# esp32_cam_rev_A.net
KiCad netlist of a schematic drawn in EAGLE
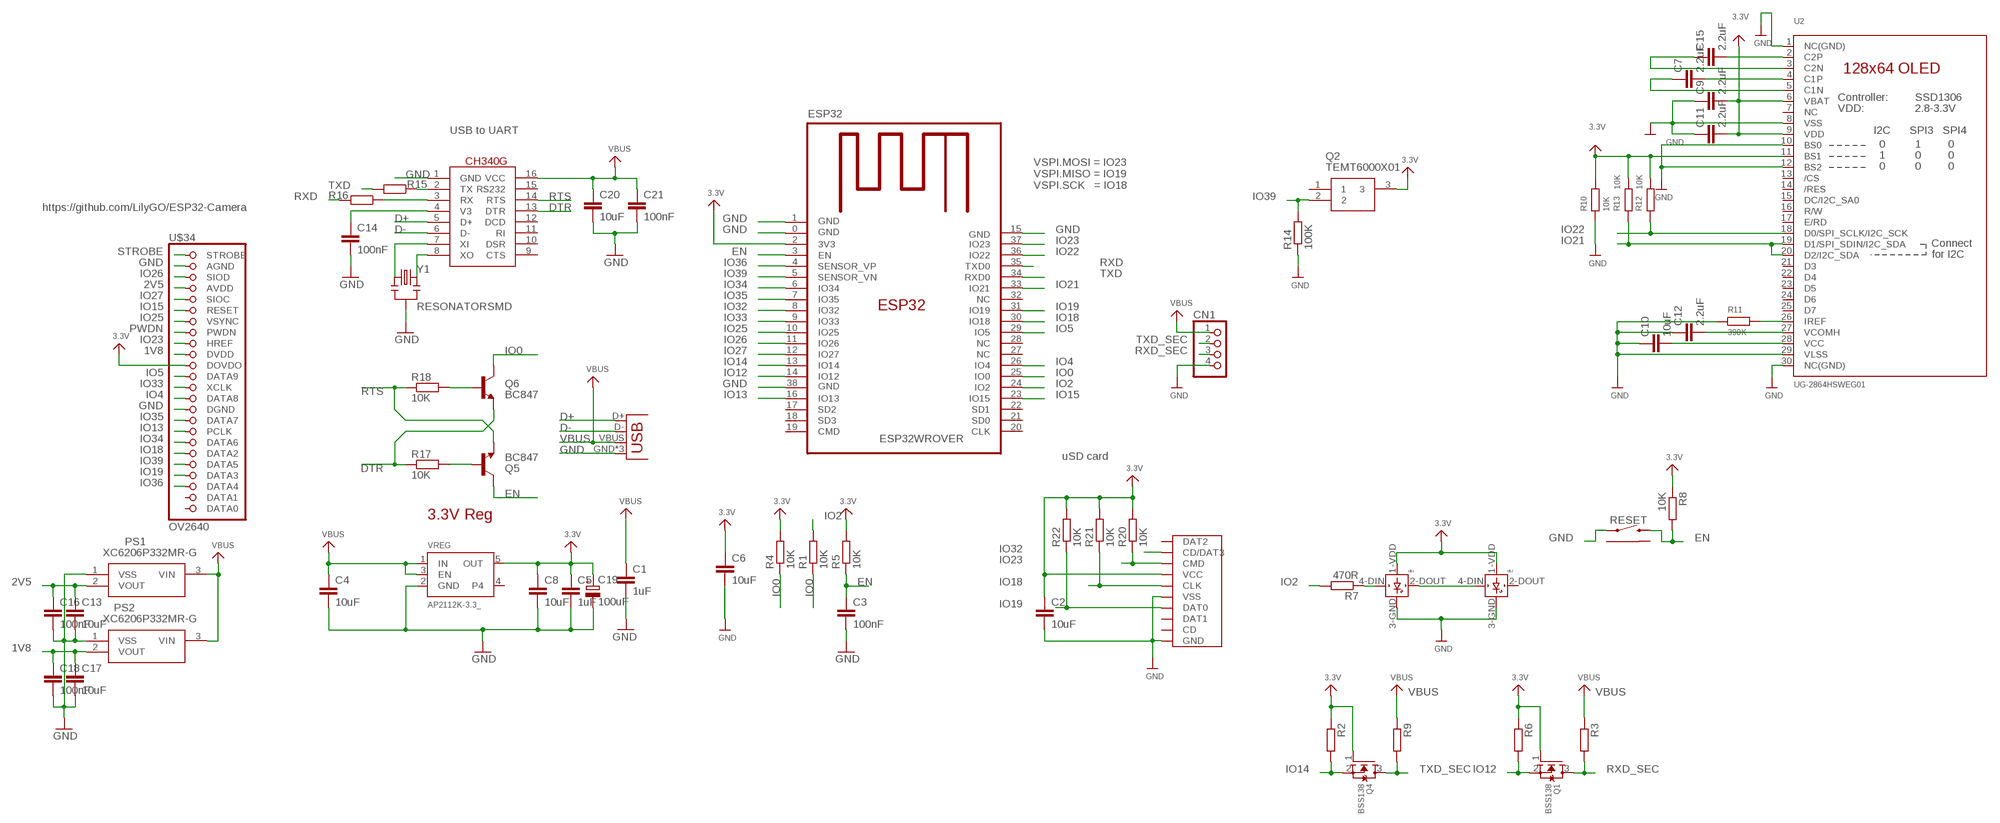
[diagram p0: schematic, sheet 1]

(export (version "E")
  (design (tool "Eeschema 10.0.6"))
  (components
    (comp (ref "C1")
      (value "1uF")
      (footprint "eagle-import:C0805K")
      (libsource (lib "eagle-import") (part "C-EUC0805K"))
    )
    (comp (ref "C2")
      (value "10uF")
      (footprint "eagle-import:C0805K")
      (libsource (lib "eagle-import") (part "C-EUC0805K"))
    )
    (comp (ref "C3")
      (value "100nF")
      (footprint "eagle-import:C0805K")
      (libsource (lib "eagle-import") (part "C-EUC0805K"))
    )
    (comp (ref "C4")
      (value "10uF")
      (footprint "eagle-import:C0805K")
      (libsource (lib "eagle-import") (part "C-EUC0805K"))
    )
    (comp (ref "C5")
      (value "1uF")
      (footprint "eagle-import:C0805K")
      (libsource (lib "eagle-import") (part "C-EUC0805K"))
    )
    (comp (ref "C6")
      (value "10uF")
      (footprint "eagle-import:C0805K")
      (libsource (lib "eagle-import") (part "C-EUC0805K"))
    )
    (comp (ref "C7")
      (value "2.2uF")
      (footprint "eagle-import:C0805")
      (libsource (lib "eagle-import") (part "C-EUC0805"))
    )
    (comp (ref "C8")
      (value "10uF")
      (footprint "eagle-import:C0805K")
      (libsource (lib "eagle-import") (part "C-EUC0805K"))
    )
    (comp (ref "C9")
      (value "2.2uF")
      (footprint "eagle-import:C0805")
      (libsource (lib "eagle-import") (part "C-EUC0805"))
    )
    (comp (ref "C10")
      (value "10uF")
      (footprint "eagle-import:C0805")
      (libsource (lib "eagle-import") (part "C-EUC0805"))
    )
    (comp (ref "C11")
      (value "2.2uF")
      (footprint "eagle-import:C0805")
      (libsource (lib "eagle-import") (part "C-EUC0805"))
    )
    (comp (ref "C12")
      (value "2.2uF")
      (footprint "eagle-import:C0805")
      (libsource (lib "eagle-import") (part "C-EUC0805"))
    )
    (comp (ref "C13")
      (value "10uF")
      (footprint "eagle-import:C0805K")
      (libsource (lib "eagle-import") (part "C-EUC0805K"))
    )
    (comp (ref "C14")
      (value "100nF")
      (footprint "eagle-import:C0805K")
      (libsource (lib "eagle-import") (part "C-EUC0805K"))
    )
    (comp (ref "C15")
      (value "2.2uF")
      (footprint "eagle-import:C0805")
      (libsource (lib "eagle-import") (part "C-EUC0805"))
    )
    (comp (ref "C16")
      (value "100nF")
      (footprint "eagle-import:C0805K")
      (libsource (lib "eagle-import") (part "C-EUC0805K"))
    )
    (comp (ref "C17")
      (value "10uF")
      (footprint "eagle-import:C0805K")
      (libsource (lib "eagle-import") (part "C-EUC0805K"))
    )
    (comp (ref "C18")
      (value "100nF")
      (footprint "eagle-import:C0805K")
      (libsource (lib "eagle-import") (part "C-EUC0805K"))
    )
    (comp (ref "C19")
      (value "100uF")
      (footprint "eagle-import:CT6032")
      (libsource (lib "eagle-import") (part "CPOL-EUCT6032"))
    )
    (comp (ref "C20")
      (value "10uF")
      (footprint "eagle-import:C0805K")
      (libsource (lib "eagle-import") (part "C-EUC0805K"))
    )
    (comp (ref "C21")
      (value "100nF")
      (footprint "eagle-import:C0805K")
      (libsource (lib "eagle-import") (part "C-EUC0805K"))
    )
    (comp (ref "CN1")
      (value "JST_PH4")
      (footprint "eagle-import:JSTPH4")
      (libsource (lib "eagle-import") (part "JST_PH4"))
    )
    (comp (ref "ESP32")
      (value "ESP32WROVER")
      (footprint "eagle-import:ESP32WROVER")
      (libsource (lib "eagle-import") (part "ESP32WROVER"))
    )
    (comp (ref "PS1")
      (value "XC6206P332MR-G")
      (footprint "eagle-import:SOT95P280X130-3N")
      (fields (field (name "MOUSER_PART_NUMBER") "865-XC6206P332MR-G"))
      (libsource (lib "eagle-import") (part "XC6206P332MR-G"))
    )
    (comp (ref "PS2")
      (value "XC6206P332MR-G")
      (footprint "eagle-import:SOT95P280X130-3N")
      (fields (field (name "MOUSER_PART_NUMBER") "865-XC6206P332MR-G"))
      (libsource (lib "eagle-import") (part "XC6206P332MR-G"))
    )
    (comp (ref "Q1")
      (value "BSS138")
      (footprint "eagle-import:SOT95P240X110-3")
      (libsource (lib "eagle-import") (part "MOSFET_N_"))
    )
    (comp (ref "Q2")
      (value "TEMT6000X01")
      (footprint "eagle-import:TEMT6000X01")
      (fields (field (name "MOUSER_PART_NUMBER") "78-TEMT6000"))
      (libsource (lib "eagle-import") (part "TEMT6000X01"))
    )
    (comp (ref "Q4")
      (value "BSS138")
      (footprint "eagle-import:SOT95P240X110-3")
      (libsource (lib "eagle-import") (part "MOSFET_N_"))
    )
    (comp (ref "Q5")
      (value "BC847")
      (footprint "eagle-import:SOT23-3")
      (libsource (lib "eagle-import") (part "TRANSISTOR_NPNSOT23-3"))
    )
    (comp (ref "Q6")
      (value "BC847")
      (footprint "eagle-import:SOT23-3")
      (libsource (lib "eagle-import") (part "TRANSISTOR_NPNSOT23-3"))
    )
    (comp (ref "R1")
      (value "10K")
      (footprint "eagle-import:R0805")
      (libsource (lib "eagle-import") (part "R-EU_R0805"))
    )
    (comp (ref "R2")
      (value "10K")
      (footprint "eagle-import:R0805")
      (libsource (lib "eagle-import") (part "R-EU_R0805"))
    )
    (comp (ref "R3")
      (value "10K")
      (footprint "eagle-import:R0805")
      (libsource (lib "eagle-import") (part "R-EU_R0805"))
    )
    (comp (ref "R4")
      (value "10K")
      (footprint "eagle-import:R0805")
      (libsource (lib "eagle-import") (part "R-EU_R0805"))
    )
    (comp (ref "R5")
      (value "10K")
      (footprint "eagle-import:R0805")
      (libsource (lib "eagle-import") (part "R-EU_R0805"))
    )
    (comp (ref "R6")
      (value "10K")
      (footprint "eagle-import:R0805")
      (libsource (lib "eagle-import") (part "R-EU_R0805"))
    )
    (comp (ref "R7")
      (value "470R")
      (footprint "eagle-import:R0805")
      (libsource (lib "eagle-import") (part "R-EU_R0805"))
    )
    (comp (ref "R8")
      (value "10K")
      (footprint "eagle-import:R0805")
      (libsource (lib "eagle-import") (part "R-EU_R0805"))
    )
    (comp (ref "R9")
      (value "10K")
      (footprint "eagle-import:R0805")
      (libsource (lib "eagle-import") (part "R-EU_R0805"))
    )
    (comp (ref "R10")
      (value "10K")
      (footprint "eagle-import:R0805")
      (libsource (lib "eagle-import") (part "R-EU_R0805"))
    )
    (comp (ref "R11")
      (value "390K")
      (footprint "eagle-import:R0805")
      (libsource (lib "eagle-import") (part "R-EU_R0805"))
    )
    (comp (ref "R12")
      (value "10K")
      (footprint "eagle-import:R0805")
      (libsource (lib "eagle-import") (part "R-EU_R0805"))
    )
    (comp (ref "R13")
      (value "10K")
      (footprint "eagle-import:R0805")
      (libsource (lib "eagle-import") (part "R-EU_R0805"))
    )
    (comp (ref "R14")
      (value "100K")
      (footprint "eagle-import:R0805")
      (libsource (lib "eagle-import") (part "R-EU_R0805"))
    )
    (comp (ref "R15")
      (value "470R")
      (footprint "eagle-import:R0805")
      (libsource (lib "eagle-import") (part "R-EU_R0805"))
    )
    (comp (ref "R16")
      (value "470R")
      (footprint "eagle-import:R0805")
      (libsource (lib "eagle-import") (part "R-EU_R0805"))
    )
    (comp (ref "R17")
      (value "10K")
      (footprint "eagle-import:R0805")
      (libsource (lib "eagle-import") (part "R-EU_R0805"))
    )
    (comp (ref "R18")
      (value "10K")
      (footprint "eagle-import:R0805")
      (libsource (lib "eagle-import") (part "R-EU_R0805"))
    )
    (comp (ref "R20")
      (value "10K")
      (footprint "eagle-import:R0805")
      (libsource (lib "eagle-import") (part "R-EU_R0805"))
    )
    (comp (ref "R21")
      (value "10K")
      (footprint "eagle-import:R0805")
      (libsource (lib "eagle-import") (part "R-EU_R0805"))
    )
    (comp (ref "R22")
      (value "10K")
      (footprint "eagle-import:R0805")
      (libsource (lib "eagle-import") (part "R-EU_R0805"))
    )
    (comp (ref "RESET")
      (value "TACTILE_SWITCH_RIGHT_ANGLE_THT\"")
      (footprint "eagle-import:TACTILE_SWITCH_RIGHT_ANGLE_THT")
      (libsource (lib "eagle-import") (part "TACTILE_SWITCH_RIGHT_ANGLE_THT{dblquote}"))
    )
    (comp (ref "SD_CARD")
      (value "MICRO_SD_CARD\"")
      (footprint "eagle-import:TFP09-2--12B")
      (libsource (lib "eagle-import") (part "MICRO_SD_CARD{dblquote}"))
    )
    (comp (ref "U$1")
      (value "WS2812B")
      (footprint "eagle-import:WS2812B_5050")
      (libsource (lib "eagle-import") (part "WS2812B"))
    )
    (comp (ref "U$2")
      (value "WS2812B")
      (footprint "eagle-import:WS2812B_5050")
      (libsource (lib "eagle-import") (part "WS2812B"))
    )
    (comp (ref "U$23")
      (value "CH340G")
      (footprint "eagle-import:SO16")
      (libsource (lib "eagle-import") (part "CH340G"))
    )
    (comp (ref "U$34")
      (value "OV2640")
      (footprint "eagle-import:FH12-24S-0.5SH")
      (libsource (lib "eagle-import") (part "OV2640"))
    )
    (comp (ref "U2")
      (value "UG-2864HSWEG01")
      (footprint "eagle-import:UG-2864HSWEG01_1.3_WRAPAROUND_MIRRORED")
      (libsource (lib "eagle-import") (part "DISP_OLED_UG-2864HSWEG01_"))
    )
    (comp (ref "USB")
      (value "USB_MICRO_ATTEND_")
      (footprint "eagle-import:USB_MICRO")
      (libsource (lib "eagle-import") (part "USB_MICRO_ATTEND_"))
    )
    (comp (ref "VREG")
      (value "AP2112K-3.3_")
      (footprint "eagle-import:SOT95P290X120-5")
      (libsource (lib "eagle-import") (part "AP2112K-3.3_"))
    )
    (comp (ref "Y1")
      (value "RESONATORSMD")
      (footprint "eagle-import:RESONATOR-SMD")
      (libsource (lib "eagle-import") (part "RESONATORSMD"))
    )
  )
  (nets
    (net (code "1") (name "/1V8") (class "Default")
      (node (ref "C17") (pin "1") (pinfunction "1_1") (pintype "passive"))
      (node (ref "C18") (pin "1") (pinfunction "1_1") (pintype "passive"))
      (node (ref "PS2") (pin "2") (pinfunction "VOUT_2") (pintype "power_in"))
      (node (ref "U$34") (pin "10") (pinfunction "DVDD_10") (pintype "passive"))
    )
    (net (code "2") (name "/2V5") (class "Default")
      (node (ref "C13") (pin "1") (pinfunction "1_1") (pintype "passive"))
      (node (ref "C16") (pin "1") (pinfunction "1_1") (pintype "passive"))
      (node (ref "PS1") (pin "2") (pinfunction "VOUT_2") (pintype "power_in"))
      (node (ref "U$34") (pin "4") (pinfunction "AVDD_4") (pintype "passive"))
    )
    (net (code "3") (name "/D+") (class "Default")
      (node (ref "U$23") (pin "5") (pinfunction "D+_5") (pintype "bidirectional"))
      (node (ref "USB") (pin "D+") (pinfunction "D+_D+") (pintype "bidirectional"))
    )
    (net (code "4") (name "/D-") (class "Default")
      (node (ref "U$23") (pin "6") (pinfunction "D-_6") (pintype "bidirectional"))
      (node (ref "USB") (pin "D-") (pinfunction "D-_D-") (pintype "bidirectional"))
    )
    (net (code "5") (name "/DTR") (class "Default")
      (node (ref "Q6") (pin "2") (pinfunction "E_2") (pintype "passive"))
      (node (ref "R17") (pin "1") (pinfunction "1_1") (pintype "passive"))
      (node (ref "U$23") (pin "13") (pinfunction "DTR_13") (pintype "bidirectional"))
    )
    (net (code "6") (name "/EN") (class "Default")
      (node (ref "C3") (pin "1") (pinfunction "1_1") (pintype "passive"))
      (node (ref "ESP32") (pin "3") (pinfunction "EN_3") (pintype "bidirectional"))
      (node (ref "Q5") (pin "3") (pinfunction "C_3") (pintype "passive"))
      (node (ref "R5") (pin "1") (pinfunction "1_1") (pintype "passive"))
      (node (ref "R8") (pin "2") (pinfunction "2_2") (pintype "passive"))
      (node (ref "RESET") (pin "2") (pinfunction "2_2") (pintype "passive"))
    )
    (net (code "7") (name "/IO0") (class "Default")
      (node (ref "ESP32") (pin "25") (pinfunction "IO0_25") (pintype "bidirectional"))
      (node (ref "Q6") (pin "3") (pinfunction "C_3") (pintype "passive"))
      (node (ref "R1") (pin "1") (pinfunction "1_1") (pintype "passive"))
      (node (ref "R4") (pin "1") (pinfunction "1_1") (pintype "passive"))
    )
    (net (code "8") (name "/IO2") (class "Default")
      (node (ref "ESP32") (pin "24") (pinfunction "IO2_24") (pintype "bidirectional"))
      (node (ref "R1") (pin "2") (pinfunction "2_2") (pintype "passive"))
      (node (ref "R7") (pin "2") (pinfunction "2_2") (pintype "passive"))
    )
    (net (code "9") (name "/IO4") (class "Default")
      (node (ref "ESP32") (pin "26") (pinfunction "IO4_26") (pintype "bidirectional"))
      (node (ref "U$34") (pin "14") (pinfunction "DATA8_14") (pintype "passive"))
    )
    (net (code "10") (name "/IO5") (class "Default")
      (node (ref "ESP32") (pin "29") (pinfunction "IO5_29") (pintype "bidirectional"))
      (node (ref "U$34") (pin "12") (pinfunction "DATA9_12") (pintype "passive"))
    )
    (net (code "11") (name "/IO12") (class "Default")
      (node (ref "ESP32") (pin "14") (pinfunction "IO12_14") (pintype "bidirectional"))
      (node (ref "Q1") (pin "2") (pinfunction "S_2") (pintype "bidirectional"))
      (node (ref "R6") (pin "2") (pinfunction "2_2") (pintype "passive"))
    )
    (net (code "12") (name "/IO13") (class "Default")
      (node (ref "ESP32") (pin "16") (pinfunction "IO13_16") (pintype "bidirectional"))
      (node (ref "U$34") (pin "17") (pinfunction "PCLK_17") (pintype "passive"))
    )
    (net (code "13") (name "/IO14") (class "Default")
      (node (ref "ESP32") (pin "13") (pinfunction "IO14_13") (pintype "bidirectional"))
      (node (ref "Q4") (pin "2") (pinfunction "S_2") (pintype "bidirectional"))
      (node (ref "R2") (pin "2") (pinfunction "2_2") (pintype "passive"))
    )
    (net (code "14") (name "/IO15") (class "Default")
      (node (ref "ESP32") (pin "23") (pinfunction "IO15_23") (pintype "bidirectional"))
      (node (ref "U$34") (pin "6") (pinfunction "RESET_6") (pintype "passive"))
    )
    (net (code "15") (name "/IO18") (class "Default")
      (node (ref "ESP32") (pin "30") (pinfunction "IO18_30") (pintype "bidirectional"))
      (node (ref "R21") (pin "1") (pinfunction "1_1") (pintype "passive"))
      (node (ref "SD_CARD") (pin "CLK") (pinfunction "CLK_CLK") (pintype "bidirectional"))
      (node (ref "U$34") (pin "19") (pinfunction "DATA2_19") (pintype "passive"))
    )
    (net (code "16") (name "/IO19") (class "Default")
      (node (ref "ESP32") (pin "31") (pinfunction "IO19_31") (pintype "bidirectional"))
      (node (ref "R22") (pin "1") (pinfunction "1_1") (pintype "passive"))
      (node (ref "SD_CARD") (pin "DAT0") (pinfunction "DAT0_DAT0") (pintype "bidirectional"))
      (node (ref "U$34") (pin "21") (pinfunction "DATA3_21") (pintype "passive"))
    )
    (net (code "17") (name "/IO21") (class "Default")
      (node (ref "ESP32") (pin "33") (pinfunction "IO21_33") (pintype "bidirectional"))
      (node (ref "R13") (pin "1") (pinfunction "1_1") (pintype "passive"))
      (node (ref "U2") (pin "19") (pinfunction "D1/SPI_SDIN/I2C_SDA_19") (pintype "bidirectional"))
      (node (ref "U2") (pin "20") (pinfunction "D2/I2C_SDA_20") (pintype "bidirectional"))
    )
    (net (code "18") (name "/IO22") (class "Default")
      (node (ref "ESP32") (pin "36") (pinfunction "IO22_36") (pintype "bidirectional"))
      (node (ref "R12") (pin "1") (pinfunction "1_1") (pintype "passive"))
      (node (ref "U2") (pin "18") (pinfunction "D0/SPI_SCLK/I2C_SCK_18") (pintype "bidirectional"))
    )
    (net (code "19") (name "/IO23") (class "Default")
      (node (ref "ESP32") (pin "37") (pinfunction "IO23_37") (pintype "bidirectional"))
      (node (ref "R20") (pin "1") (pinfunction "1_1") (pintype "passive"))
      (node (ref "SD_CARD") (pin "CMD") (pinfunction "CMD_CMD") (pintype "bidirectional"))
      (node (ref "U$34") (pin "9") (pinfunction "HREF_9") (pintype "passive"))
    )
    (net (code "20") (name "/IO25") (class "Default")
      (node (ref "ESP32") (pin "10") (pinfunction "IO25_10") (pintype "bidirectional"))
      (node (ref "U$34") (pin "7") (pinfunction "VSYNC_7") (pintype "passive"))
    )
    (net (code "21") (name "/IO26") (class "Default")
      (node (ref "ESP32") (pin "11") (pinfunction "IO26_11") (pintype "bidirectional"))
      (node (ref "U$34") (pin "3") (pinfunction "SIOD_3") (pintype "passive"))
    )
    (net (code "22") (name "/IO27") (class "Default")
      (node (ref "ESP32") (pin "12") (pinfunction "IO27_12") (pintype "bidirectional"))
      (node (ref "U$34") (pin "5") (pinfunction "SIOC_5") (pintype "passive"))
    )
    (net (code "23") (name "/IO32") (class "Default")
      (node (ref "ESP32") (pin "8") (pinfunction "IO32_8") (pintype "bidirectional"))
      (node (ref "SD_CARD") (pin "CD/DAT3") (pinfunction "CD/DAT3_CD/DAT3") (pintype "bidirectional"))
    )
    (net (code "24") (name "/IO33") (class "Default")
      (node (ref "ESP32") (pin "9") (pinfunction "IO33_9") (pintype "bidirectional"))
      (node (ref "U$34") (pin "13") (pinfunction "XCLK_13") (pintype "passive"))
    )
    (net (code "25") (name "/IO34") (class "Default")
      (node (ref "ESP32") (pin "6") (pinfunction "IO34_6") (pintype "bidirectional"))
      (node (ref "U$34") (pin "18") (pinfunction "DATA6_18") (pintype "passive"))
    )
    (net (code "26") (name "/IO35") (class "Default")
      (node (ref "ESP32") (pin "7") (pinfunction "IO35_7") (pintype "bidirectional"))
      (node (ref "U$34") (pin "16") (pinfunction "DATA7_16") (pintype "passive"))
    )
    (net (code "27") (name "/IO36") (class "Default")
      (node (ref "ESP32") (pin "4") (pinfunction "SENSOR_VP_4") (pintype "bidirectional"))
      (node (ref "U$34") (pin "22") (pinfunction "DATA4_22") (pintype "passive"))
    )
    (net (code "28") (name "/IO39") (class "Default")
      (node (ref "ESP32") (pin "5") (pinfunction "SENSOR_VN_5") (pintype "bidirectional"))
      (node (ref "Q2") (pin "2") (pinfunction "2_2") (pintype "bidirectional"))
      (node (ref "R14") (pin "2") (pinfunction "2_2") (pintype "passive"))
      (node (ref "U$34") (pin "20") (pinfunction "DATA5_20") (pintype "passive"))
    )
    (net (code "29") (name "/PWDN") (class "Default")
      (node (ref "U$34") (pin "8") (pinfunction "PWDN_8") (pintype "passive"))
    )
    (net (code "30") (name "/RTS") (class "Default")
      (node (ref "Q5") (pin "2") (pinfunction "E_2") (pintype "passive"))
      (node (ref "R18") (pin "1") (pinfunction "1_1") (pintype "passive"))
      (node (ref "U$23") (pin "14") (pinfunction "RTS_14") (pintype "bidirectional"))
    )
    (net (code "31") (name "/RXD") (class "Default")
      (node (ref "ESP32") (pin "35") (pinfunction "TXD0_35") (pintype "bidirectional"))
      (node (ref "R16") (pin "2") (pinfunction "2_2") (pintype "passive"))
    )
    (net (code "32") (name "/RXD_SEC") (class "Default")
      (node (ref "CN1") (pin "3") (pinfunction "3_3") (pintype "passive"))
      (node (ref "Q1") (pin "3") (pinfunction "D_3") (pintype "bidirectional"))
      (node (ref "R3") (pin "2") (pinfunction "2_2") (pintype "passive"))
    )
    (net (code "33") (name "/STROBE") (class "Default")
      (node (ref "U$34") (pin "1") (pinfunction "STROBE_1") (pintype "passive"))
    )
    (net (code "34") (name "/TXD") (class "Default")
      (node (ref "ESP32") (pin "34") (pinfunction "RXD0_34") (pintype "bidirectional"))
      (node (ref "R15") (pin "2") (pinfunction "2_2") (pintype "passive"))
    )
    (net (code "35") (name "/TXD_SEC") (class "Default")
      (node (ref "CN1") (pin "2") (pinfunction "2_2") (pintype "passive"))
      (node (ref "Q4") (pin "3") (pinfunction "D_3") (pintype "bidirectional"))
      (node (ref "R9") (pin "2") (pinfunction "2_2") (pintype "passive"))
    )
    (net (code "36") (name "3.3V") (class "Default")
      (node (ref "C11") (pin "2") (pinfunction "2_2") (pintype "passive"))
      (node (ref "C19") (pin "+") (pinfunction "+_+") (pintype "passive"))
      (node (ref "C2") (pin "1") (pinfunction "1_1") (pintype "passive"))
      (node (ref "C5") (pin "1") (pinfunction "1_1") (pintype "passive"))
      (node (ref "C6") (pin "1") (pinfunction "1_1") (pintype "passive"))
      (node (ref "C8") (pin "1") (pinfunction "1_1") (pintype "passive"))
      (node (ref "C9") (pin "2") (pinfunction "2_2") (pintype "passive"))
      (node (ref "ESP32") (pin "2") (pinfunction "3V3_2") (pintype "power_in"))
      (node (ref "Q1") (pin "1") (pinfunction "G_1") (pintype "bidirectional"))
      (node (ref "Q2") (pin "3") (pinfunction "3_3") (pintype "bidirectional"))
      (node (ref "Q4") (pin "1") (pinfunction "G_1") (pintype "bidirectional"))
      (node (ref "R10") (pin "2") (pinfunction "2_2") (pintype "passive"))
      (node (ref "R12") (pin "2") (pinfunction "2_2") (pintype "passive"))
      (node (ref "R13") (pin "2") (pinfunction "2_2") (pintype "passive"))
      (node (ref "R2") (pin "1") (pinfunction "1_1") (pintype "passive"))
      (node (ref "R20") (pin "2") (pinfunction "2_2") (pintype "passive"))
      (node (ref "R21") (pin "2") (pinfunction "2_2") (pintype "passive"))
      (node (ref "R22") (pin "2") (pinfunction "2_2") (pintype "passive"))
      (node (ref "R4") (pin "2") (pinfunction "2_2") (pintype "passive"))
      (node (ref "R5") (pin "2") (pinfunction "2_2") (pintype "passive"))
      (node (ref "R6") (pin "1") (pinfunction "1_1") (pintype "passive"))
      (node (ref "R8") (pin "1") (pinfunction "1_1") (pintype "passive"))
      (node (ref "SD_CARD") (pin "VCC") (pinfunction "VCC_VCC") (pintype "bidirectional"))
      (node (ref "U$1") (pin "1-VDD") (pinfunction "VDD_1-VDD") (pintype "power_in"))
      (node (ref "U$2") (pin "1-VDD") (pinfunction "VDD_1-VDD") (pintype "power_in"))
      (node (ref "U$34") (pin "11") (pinfunction "DOVDO_11") (pintype "passive"))
      (node (ref "U2") (pin "11") (pinfunction "BS1_11") (pintype "input"))
      (node (ref "U2") (pin "6") (pinfunction "VBAT_6") (pintype "input"))
      (node (ref "U2") (pin "9") (pinfunction "VDD_9") (pintype "power_in"))
      (node (ref "VREG") (pin "5") (pinfunction "OUT_5") (pintype "bidirectional"))
    )
    (net (code "37") (name "GND") (class "Default")
      (node (ref "C1") (pin "2") (pinfunction "2_2") (pintype "passive"))
      (node (ref "C10") (pin "1") (pinfunction "1_1") (pintype "passive"))
      (node (ref "C11") (pin "1") (pinfunction "1_1") (pintype "passive"))
      (node (ref "C12") (pin "1") (pinfunction "1_1") (pintype "passive"))
      (node (ref "C13") (pin "2") (pinfunction "2_2") (pintype "passive"))
      (node (ref "C14") (pin "2") (pinfunction "2_2") (pintype "passive"))
      (node (ref "C16") (pin "2") (pinfunction "2_2") (pintype "passive"))
      (node (ref "C17") (pin "2") (pinfunction "2_2") (pintype "passive"))
      (node (ref "C18") (pin "2") (pinfunction "2_2") (pintype "passive"))
      (node (ref "C19") (pin "-") (pinfunction "-_-") (pintype "passive"))
      (node (ref "C2") (pin "2") (pinfunction "2_2") (pintype "passive"))
      (node (ref "C20") (pin "2") (pinfunction "2_2") (pintype "passive"))
      (node (ref "C21") (pin "2") (pinfunction "2_2") (pintype "passive"))
      (node (ref "C3") (pin "2") (pinfunction "2_2") (pintype "passive"))
      (node (ref "C4") (pin "2") (pinfunction "2_2") (pintype "passive"))
      (node (ref "C5") (pin "2") (pinfunction "2_2") (pintype "passive"))
      (node (ref "C6") (pin "2") (pinfunction "2_2") (pintype "passive"))
      (node (ref "C8") (pin "2") (pinfunction "2_2") (pintype "passive"))
      (node (ref "C9") (pin "1") (pinfunction "1_1") (pintype "passive"))
      (node (ref "CN1") (pin "4") (pinfunction "4_4") (pintype "passive"))
      (node (ref "ESP32") (pin "0") (pinfunction "GND_0") (pintype "power_in"))
      (node (ref "ESP32") (pin "1") (pinfunction "GND_1") (pintype "power_in"))
      (node (ref "ESP32") (pin "15") (pinfunction "GND_15") (pintype "power_in"))
      (node (ref "ESP32") (pin "38") (pinfunction "GND_38") (pintype "power_in"))
      (node (ref "PS1") (pin "1") (pinfunction "VSS_1") (pintype "power_in"))
      (node (ref "PS2") (pin "1") (pinfunction "VSS_1") (pintype "power_in"))
      (node (ref "R10") (pin "1") (pinfunction "1_1") (pintype "passive"))
      (node (ref "R11") (pin "1") (pinfunction "1_1") (pintype "passive"))
      (node (ref "R14") (pin "1") (pinfunction "1_1") (pintype "passive"))
      (node (ref "RESET") (pin "1") (pinfunction "1_1") (pintype "passive"))
      (node (ref "SD_CARD") (pin "GND") (pinfunction "GND_GND") (pintype "bidirectional"))
      (node (ref "SD_CARD") (pin "GND@1") (pinfunction "GND_GND@1") (pintype "bidirectional"))
      (node (ref "SD_CARD") (pin "GND@2") (pinfunction "GND_GND@2") (pintype "bidirectional"))
      (node (ref "SD_CARD") (pin "GND@3") (pinfunction "VSS_GND@3") (pintype "bidirectional"))
      (node (ref "SD_CARD") (pin "VSS") (pinfunction "GND_VSS") (pintype "bidirectional"))
      (node (ref "U$1") (pin "3-GND") (pinfunction "GND_3-GND") (pintype "power_in"))
      (node (ref "U$2") (pin "3-GND") (pinfunction "GND_3-GND") (pintype "power_in"))
      (node (ref "U$23") (pin "1") (pinfunction "GND_1") (pintype "bidirectional"))
      (node (ref "U$34") (pin "15") (pinfunction "DGND_15") (pintype "passive"))
      (node (ref "U$34") (pin "2") (pinfunction "AGND_2") (pintype "passive"))
      (node (ref "U2") (pin "1") (pinfunction "NC(GND)_1") (pintype "input"))
      (node (ref "U2") (pin "10") (pinfunction "BS0_10") (pintype "input"))
      (node (ref "U2") (pin "12") (pinfunction "BS2_12") (pintype "input"))
      (node (ref "U2") (pin "29") (pinfunction "VLSS_29") (pintype "power_in"))
      (node (ref "U2") (pin "30") (pinfunction "NC(GND)_30") (pintype "input"))
      (node (ref "U2") (pin "8") (pinfunction "VSS_8") (pintype "power_in"))
      (node (ref "USB") (pin "GND") (pinfunction "GND_GND") (pintype "bidirectional"))
      (node (ref "USB") (pin "GND@2") (pinfunction "GND_GND@2") (pintype "bidirectional"))
      (node (ref "USB") (pin "GND@3") (pinfunction "GND_GND@3") (pintype "bidirectional"))
      (node (ref "VREG") (pin "2") (pinfunction "GND_2") (pintype "bidirectional"))
      (node (ref "Y1") (pin "2") (pinfunction "2_2") (pintype "passive"))
    )
    (net (code "38") (name "Net-(Q5-B)") (class "Default")
      (node (ref "Q5") (pin "1") (pinfunction "B_1") (pintype "passive"))
      (node (ref "R17") (pin "2") (pinfunction "2_2") (pintype "passive"))
    )
    (net (code "39") (name "Net-(Q6-B)") (class "Default")
      (node (ref "Q6") (pin "1") (pinfunction "B_1") (pintype "passive"))
      (node (ref "R18") (pin "2") (pinfunction "2_2") (pintype "passive"))
    )
    (net (code "40") (name "Net-(U$1-DIN)") (class "Default")
      (node (ref "R7") (pin "1") (pinfunction "1_1") (pintype "passive"))
      (node (ref "U$1") (pin "4-DIN") (pinfunction "DIN_4-DIN") (pintype "input"))
    )
    (net (code "41") (name "Net-(U$1-DOUT)") (class "Default")
      (node (ref "U$1") (pin "2-DOUT") (pinfunction "DOUT_2-DOUT") (pintype "output"))
      (node (ref "U$2") (pin "4-DIN") (pinfunction "DIN_4-DIN") (pintype "input"))
    )
    (net (code "42") (name "Net-(U$23-RX)") (class "Default")
      (node (ref "R16") (pin "1") (pinfunction "1_1") (pintype "passive"))
      (node (ref "U$23") (pin "3") (pinfunction "RX_3") (pintype "bidirectional"))
    )
    (net (code "43") (name "Net-(U$23-TX)") (class "Default")
      (node (ref "R15") (pin "1") (pinfunction "1_1") (pintype "passive"))
      (node (ref "U$23") (pin "2") (pinfunction "TX_2") (pintype "bidirectional"))
    )
    (net (code "44") (name "Net-(U$23-V3)") (class "Default")
      (node (ref "C14") (pin "1") (pinfunction "1_1") (pintype "passive"))
      (node (ref "U$23") (pin "4") (pinfunction "V3_4") (pintype "bidirectional"))
    )
    (net (code "45") (name "Net-(U$23-XI)") (class "Default")
      (node (ref "U$23") (pin "7") (pinfunction "XI_7") (pintype "bidirectional"))
      (node (ref "Y1") (pin "1") (pinfunction "1_1") (pintype "passive"))
    )
    (net (code "46") (name "Net-(U$23-XO)") (class "Default")
      (node (ref "U$23") (pin "8") (pinfunction "XO_8") (pintype "bidirectional"))
      (node (ref "Y1") (pin "3") (pinfunction "3_3") (pintype "passive"))
    )
    (net (code "47") (name "Net-(U2-C1N)") (class "Default")
      (node (ref "C7") (pin "1") (pinfunction "1_1") (pintype "passive"))
      (node (ref "U2") (pin "5") (pinfunction "C1N_5") (pintype "input"))
    )
    (net (code "48") (name "Net-(U2-C1P)") (class "Default")
      (node (ref "C7") (pin "2") (pinfunction "2_2") (pintype "passive"))
      (node (ref "U2") (pin "4") (pinfunction "C1P_4") (pintype "input"))
    )
    (net (code "49") (name "Net-(U2-C2N)") (class "Default")
      (node (ref "C15") (pin "1") (pinfunction "1_1") (pintype "passive"))
      (node (ref "U2") (pin "3") (pinfunction "C2N_3") (pintype "input"))
    )
    (net (code "50") (name "Net-(U2-C2P)") (class "Default")
      (node (ref "C15") (pin "2") (pinfunction "2_2") (pintype "passive"))
      (node (ref "U2") (pin "2") (pinfunction "C2P_2") (pintype "input"))
    )
    (net (code "51") (name "Net-(U2-IREF)") (class "Default")
      (node (ref "R11") (pin "2") (pinfunction "2_2") (pintype "passive"))
      (node (ref "U2") (pin "26") (pinfunction "IREF_26") (pintype "input"))
    )
    (net (code "52") (name "Net-(U2-VCC)") (class "Default")
      (node (ref "C10") (pin "2") (pinfunction "2_2") (pintype "passive"))
      (node (ref "U2") (pin "28") (pinfunction "VCC_28") (pintype "power_in"))
    )
    (net (code "53") (name "Net-(U2-VCOMH)") (class "Default")
      (node (ref "C12") (pin "2") (pinfunction "2_2") (pintype "passive"))
      (node (ref "U2") (pin "27") (pinfunction "VCOMH_27") (pintype "output"))
    )
    (net (code "54") (name "VBUS") (class "Default")
      (node (ref "C1") (pin "1") (pinfunction "1_1") (pintype "passive"))
      (node (ref "C20") (pin "1") (pinfunction "1_1") (pintype "passive"))
      (node (ref "C21") (pin "1") (pinfunction "1_1") (pintype "passive"))
      (node (ref "C4") (pin "1") (pinfunction "1_1") (pintype "passive"))
      (node (ref "CN1") (pin "1") (pinfunction "1_1") (pintype "passive"))
      (node (ref "PS1") (pin "3") (pinfunction "VIN_3") (pintype "power_in"))
      (node (ref "PS2") (pin "3") (pinfunction "VIN_3") (pintype "power_in"))
      (node (ref "R3") (pin "1") (pinfunction "1_1") (pintype "passive"))
      (node (ref "R9") (pin "1") (pinfunction "1_1") (pintype "passive"))
      (node (ref "U$23") (pin "16") (pinfunction "VCC_16") (pintype "bidirectional"))
      (node (ref "USB") (pin "VBUS") (pinfunction "VBUS_VBUS") (pintype "bidirectional"))
      (node (ref "VREG") (pin "1") (pinfunction "IN_1") (pintype "bidirectional"))
      (node (ref "VREG") (pin "3") (pinfunction "EN_3") (pintype "bidirectional"))
    )
    (net (code "55") (name "unconnected-(ESP32-CLK-Pad20)") (class "Default")
      (node (ref "ESP32") (pin "20") (pinfunction "CLK_20") (pintype "bidirectional"))
    )
    (net (code "56") (name "unconnected-(ESP32-CMD-Pad19)") (class "Default")
      (node (ref "ESP32") (pin "19") (pinfunction "CMD_19") (pintype "bidirectional"))
    )
    (net (code "57") (name "unconnected-(ESP32-NC-Pad27)") (class "Default")
      (node (ref "ESP32") (pin "27") (pinfunction "NC_27") (pintype "bidirectional"))
    )
    (net (code "58") (name "unconnected-(ESP32-NC-Pad28)") (class "Default")
      (node (ref "ESP32") (pin "28") (pinfunction "NC_28") (pintype "bidirectional"))
    )
    (net (code "59") (name "unconnected-(ESP32-NC-Pad32)") (class "Default")
      (node (ref "ESP32") (pin "32") (pinfunction "NC_32") (pintype "bidirectional"))
    )
    (net (code "60") (name "unconnected-(ESP32-SD0-Pad21)") (class "Default")
      (node (ref "ESP32") (pin "21") (pinfunction "SD0_21") (pintype "bidirectional"))
    )
    (net (code "61") (name "unconnected-(ESP32-SD1-Pad22)") (class "Default")
      (node (ref "ESP32") (pin "22") (pinfunction "SD1_22") (pintype "bidirectional"))
    )
    (net (code "62") (name "unconnected-(ESP32-SD2-Pad17)") (class "Default")
      (node (ref "ESP32") (pin "17") (pinfunction "SD2_17") (pintype "bidirectional"))
    )
    (net (code "63") (name "unconnected-(ESP32-SD3-Pad18)") (class "Default")
      (node (ref "ESP32") (pin "18") (pinfunction "SD3_18") (pintype "bidirectional"))
    )
    (net (code "64") (name "unconnected-(Q2-Pad1)") (class "Default")
      (node (ref "Q2") (pin "1") (pinfunction "1_1") (pintype "bidirectional"))
    )
    (net (code "65") (name "unconnected-(RESET-3-PadANCHOR1)") (class "Default")
      (node (ref "RESET") (pin "ANCHOR1") (pinfunction "3_ANCHOR1") (pintype "passive"))
    )
    (net (code "66") (name "unconnected-(RESET-4-PadANCHOR2)") (class "Default")
      (node (ref "RESET") (pin "ANCHOR2") (pinfunction "4_ANCHOR2") (pintype "passive"))
    )
    (net (code "67") (name "unconnected-(SD_CARD-PadCD)") (class "Default")
      (node (ref "SD_CARD") (pin "CD") (pinfunction "CD_CD") (pintype "bidirectional"))
    )
    (net (code "68") (name "unconnected-(SD_CARD-PadDAT1)") (class "Default")
      (node (ref "SD_CARD") (pin "DAT1") (pinfunction "DAT1_DAT1") (pintype "bidirectional"))
    )
    (net (code "69") (name "unconnected-(SD_CARD-PadDAT2)") (class "Default")
      (node (ref "SD_CARD") (pin "DAT2") (pinfunction "DAT2_DAT2") (pintype "bidirectional"))
    )
    (net (code "70") (name "unconnected-(U$2-DOUT-Pad2-DOUT)") (class "Default")
      (node (ref "U$2") (pin "2-DOUT") (pinfunction "DOUT_2-DOUT") (pintype "output"))
    )
    (net (code "71") (name "unconnected-(U$23-CTS-Pad9)") (class "Default")
      (node (ref "U$23") (pin "9") (pinfunction "CTS_9") (pintype "bidirectional"))
    )
    (net (code "72") (name "unconnected-(U$23-DCD-Pad12)") (class "Default")
      (node (ref "U$23") (pin "12") (pinfunction "DCD_12") (pintype "bidirectional"))
    )
    (net (code "73") (name "unconnected-(U$23-DSR-Pad10)") (class "Default")
      (node (ref "U$23") (pin "10") (pinfunction "DSR_10") (pintype "bidirectional"))
    )
    (net (code "74") (name "unconnected-(U$23-RI-Pad11)") (class "Default")
      (node (ref "U$23") (pin "11") (pinfunction "RI_11") (pintype "bidirectional"))
    )
    (net (code "75") (name "unconnected-(U$23-RS232-Pad15)") (class "Default")
      (node (ref "U$23") (pin "15") (pinfunction "RS232_15") (pintype "bidirectional"))
    )
    (net (code "76") (name "unconnected-(U$34-DATA0-Pad24)") (class "Default")
      (node (ref "U$34") (pin "24") (pinfunction "DATA0_24") (pintype "passive"))
    )
    (net (code "77") (name "unconnected-(U$34-DATA1-Pad23)") (class "Default")
      (node (ref "U$34") (pin "23") (pinfunction "DATA1_23") (pintype "passive"))
    )
    (net (code "78") (name "unconnected-(U2-D3-Pad21)") (class "Default")
      (node (ref "U2") (pin "21") (pinfunction "D3_21") (pintype "bidirectional"))
    )
    (net (code "79") (name "unconnected-(U2-D4-Pad22)") (class "Default")
      (node (ref "U2") (pin "22") (pinfunction "D4_22") (pintype "bidirectional"))
    )
    (net (code "80") (name "unconnected-(U2-D5-Pad23)") (class "Default")
      (node (ref "U2") (pin "23") (pinfunction "D5_23") (pintype "bidirectional"))
    )
    (net (code "81") (name "unconnected-(U2-D6-Pad24)") (class "Default")
      (node (ref "U2") (pin "24") (pinfunction "D6_24") (pintype "bidirectional"))
    )
    (net (code "82") (name "unconnected-(U2-D7-Pad25)") (class "Default")
      (node (ref "U2") (pin "25") (pinfunction "D7_25") (pintype "bidirectional"))
    )
    (net (code "83") (name "unconnected-(U2-DC{slash}I2C_SA0-Pad15)") (class "Default")
      (node (ref "U2") (pin "15") (pinfunction "DC/I2C_SA0_15") (pintype "input"))
    )
    (net (code "84") (name "unconnected-(U2-E{slash}RD-Pad17)") (class "Default")
      (node (ref "U2") (pin "17") (pinfunction "E/RD_17") (pintype "input"))
    )
    (net (code "85") (name "unconnected-(U2-NC-Pad7)") (class "Default")
      (node (ref "U2") (pin "7") (pinfunction "NC_7") (pintype "no_connect"))
    )
    (net (code "86") (name "unconnected-(U2-R{slash}W-Pad16)") (class "Default")
      (node (ref "U2") (pin "16") (pinfunction "R/W_16") (pintype "input"))
    )
    (net (code "87") (name "unconnected-(U2-{slash}CS-Pad13)") (class "Default")
      (node (ref "U2") (pin "13") (pinfunction "/CS_13") (pintype "input"))
    )
    (net (code "88") (name "unconnected-(U2-{slash}RES-Pad14)") (class "Default")
      (node (ref "U2") (pin "14") (pinfunction "/RES_14") (pintype "input"))
    )
    (net (code "89") (name "unconnected-(VREG-P4-Pad4)") (class "Default")
      (node (ref "VREG") (pin "4") (pinfunction "P4_4") (pintype "bidirectional"))
    )
  )
)
